# dragonjoy.net
KiCad netlist of a schematic drawn in EAGLE
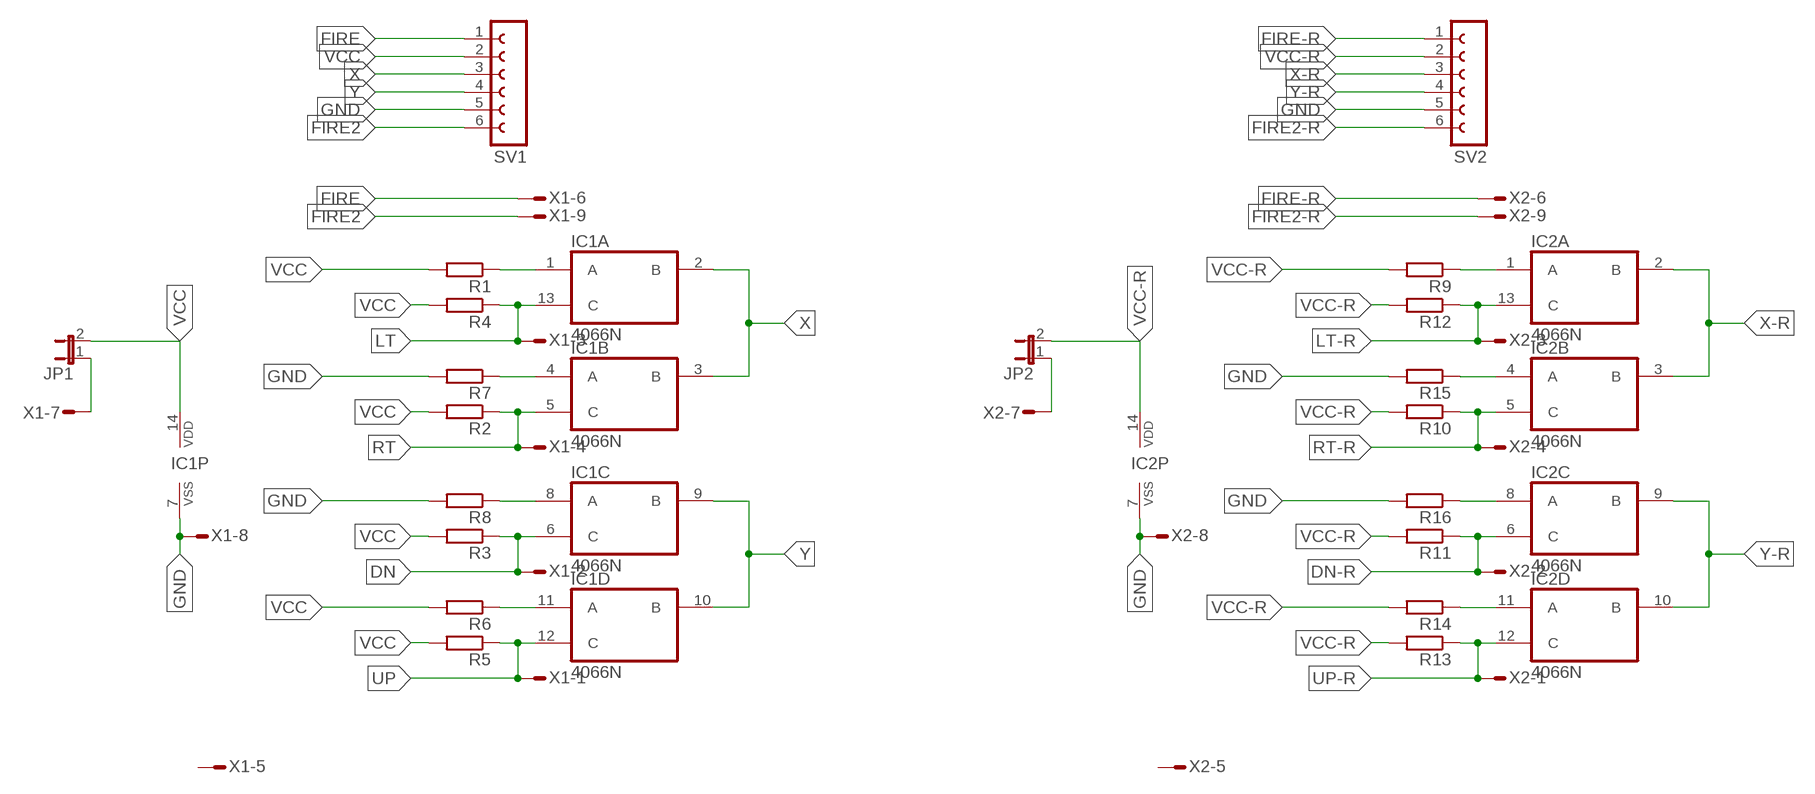
[diagram p0: schematic, sheet 1]

(export (version "E")
  (design (tool "Eeschema 10.0.6"))
  (components
    (comp (ref "IC1")
      (value "4066N")
      (footprint "eagle-import:DIL14")
      (libsource (lib "eagle-import") (part "4066N"))
    )
    (comp (ref "IC2")
      (value "4066N")
      (footprint "eagle-import:DIL14")
      (libsource (lib "eagle-import") (part "4066N"))
    )
    (comp (ref "JP1")
      (value "JP1E")
      (footprint "eagle-import:JP1")
      (libsource (lib "eagle-import") (part "JP1E"))
    )
    (comp (ref "JP2")
      (value "JP1E")
      (footprint "eagle-import:JP1")
      (libsource (lib "eagle-import") (part "JP1E"))
    )
    (comp (ref "R1")
      (value "R-EU_0207/10")
      (footprint "eagle-import:0207_10")
      (libsource (lib "eagle-import") (part "R-EU_0207/10"))
    )
    (comp (ref "R2")
      (value "R-EU_0207/10")
      (footprint "eagle-import:0207_10")
      (libsource (lib "eagle-import") (part "R-EU_0207/10"))
    )
    (comp (ref "R3")
      (value "R-EU_0207/10")
      (footprint "eagle-import:0207_10")
      (libsource (lib "eagle-import") (part "R-EU_0207/10"))
    )
    (comp (ref "R4")
      (value "R-EU_0207/10")
      (footprint "eagle-import:0207_10")
      (libsource (lib "eagle-import") (part "R-EU_0207/10"))
    )
    (comp (ref "R5")
      (value "R-EU_0207/10")
      (footprint "eagle-import:0207_10")
      (libsource (lib "eagle-import") (part "R-EU_0207/10"))
    )
    (comp (ref "R6")
      (value "R-EU_0207/10")
      (footprint "eagle-import:0207_10")
      (libsource (lib "eagle-import") (part "R-EU_0207/10"))
    )
    (comp (ref "R7")
      (value "R-EU_0207/10")
      (footprint "eagle-import:0207_10")
      (libsource (lib "eagle-import") (part "R-EU_0207/10"))
    )
    (comp (ref "R8")
      (value "R-EU_0207/10")
      (footprint "eagle-import:0207_10")
      (libsource (lib "eagle-import") (part "R-EU_0207/10"))
    )
    (comp (ref "R9")
      (value "R-EU_0207/10")
      (footprint "eagle-import:0207_10")
      (libsource (lib "eagle-import") (part "R-EU_0207/10"))
    )
    (comp (ref "R10")
      (value "R-EU_0207/10")
      (footprint "eagle-import:0207_10")
      (libsource (lib "eagle-import") (part "R-EU_0207/10"))
    )
    (comp (ref "R11")
      (value "R-EU_0207/10")
      (footprint "eagle-import:0207_10")
      (libsource (lib "eagle-import") (part "R-EU_0207/10"))
    )
    (comp (ref "R12")
      (value "R-EU_0207/10")
      (footprint "eagle-import:0207_10")
      (libsource (lib "eagle-import") (part "R-EU_0207/10"))
    )
    (comp (ref "R13")
      (value "R-EU_0207/10")
      (footprint "eagle-import:0207_10")
      (libsource (lib "eagle-import") (part "R-EU_0207/10"))
    )
    (comp (ref "R14")
      (value "R-EU_0207/10")
      (footprint "eagle-import:0207_10")
      (libsource (lib "eagle-import") (part "R-EU_0207/10"))
    )
    (comp (ref "R15")
      (value "R-EU_0207/10")
      (footprint "eagle-import:0207_10")
      (libsource (lib "eagle-import") (part "R-EU_0207/10"))
    )
    (comp (ref "R16")
      (value "R-EU_0207/10")
      (footprint "eagle-import:0207_10")
      (libsource (lib "eagle-import") (part "R-EU_0207/10"))
    )
    (comp (ref "SV1")
      (value "FE06-1")
      (footprint "eagle-import:FE06")
      (libsource (lib "eagle-import") (part "FE06-1"))
    )
    (comp (ref "SV2")
      (value "FE06-1")
      (footprint "eagle-import:FE06")
      (libsource (lib "eagle-import") (part "FE06-1"))
    )
    (comp (ref "X1")
      (value "M09-182S")
      (footprint "eagle-import:182-009-MALE")
      (libsource (lib "eagle-import") (part "M09?S-182"))
    )
    (comp (ref "X2")
      (value "M09-182S")
      (footprint "eagle-import:182-009-MALE")
      (libsource (lib "eagle-import") (part "M09?S-182"))
    )
  )
  (nets
    (net (code "1") (name "DN") (class "Default")
      (node (ref "IC1") (pin "6") (pinfunction "C_6") (pintype "input"))
      (node (ref "R3") (pin "1") (pinfunction "1_1") (pintype "passive"))
      (node (ref "X1") (pin "2") (pinfunction "M_2") (pintype "passive"))
    )
    (net (code "2") (name "DN-R") (class "Default")
      (node (ref "IC2") (pin "6") (pinfunction "C_6") (pintype "input"))
      (node (ref "R11") (pin "1") (pinfunction "1_1") (pintype "passive"))
      (node (ref "X2") (pin "2") (pinfunction "M_2") (pintype "passive"))
    )
    (net (code "3") (name "FIRE") (class "Default")
      (node (ref "SV1") (pin "1") (pinfunction "1_1") (pintype "passive"))
      (node (ref "X1") (pin "6") (pinfunction "M_6") (pintype "passive"))
    )
    (net (code "4") (name "FIRE-R") (class "Default")
      (node (ref "SV2") (pin "1") (pinfunction "1_1") (pintype "passive"))
      (node (ref "X2") (pin "6") (pinfunction "M_6") (pintype "passive"))
    )
    (net (code "5") (name "FIRE2") (class "Default")
      (node (ref "SV1") (pin "6") (pinfunction "6_6") (pintype "passive"))
      (node (ref "X1") (pin "9") (pinfunction "M_9") (pintype "passive"))
    )
    (net (code "6") (name "FIRE2-R") (class "Default")
      (node (ref "SV2") (pin "6") (pinfunction "6_6") (pintype "passive"))
      (node (ref "X2") (pin "9") (pinfunction "M_9") (pintype "passive"))
    )
    (net (code "7") (name "GND") (class "Default")
      (node (ref "IC1") (pin "7") (pinfunction "VSS_7") (pintype "power_in"))
      (node (ref "IC2") (pin "7") (pinfunction "VSS_7") (pintype "power_in"))
      (node (ref "R15") (pin "2") (pinfunction "2_2") (pintype "passive"))
      (node (ref "R16") (pin "2") (pinfunction "2_2") (pintype "passive"))
      (node (ref "R7") (pin "2") (pinfunction "2_2") (pintype "passive"))
      (node (ref "R8") (pin "2") (pinfunction "2_2") (pintype "passive"))
      (node (ref "SV1") (pin "5") (pinfunction "5_5") (pintype "passive"))
      (node (ref "SV2") (pin "5") (pinfunction "5_5") (pintype "passive"))
      (node (ref "X1") (pin "8") (pinfunction "M_8") (pintype "passive"))
      (node (ref "X2") (pin "8") (pinfunction "M_8") (pintype "passive"))
    )
    (net (code "8") (name "LT") (class "Default")
      (node (ref "IC1") (pin "13") (pinfunction "C_13") (pintype "input"))
      (node (ref "R4") (pin "1") (pinfunction "1_1") (pintype "passive"))
      (node (ref "X1") (pin "3") (pinfunction "M_3") (pintype "passive"))
    )
    (net (code "9") (name "LT-R") (class "Default")
      (node (ref "IC2") (pin "13") (pinfunction "C_13") (pintype "input"))
      (node (ref "R12") (pin "1") (pinfunction "1_1") (pintype "passive"))
      (node (ref "X2") (pin "3") (pinfunction "M_3") (pintype "passive"))
    )
    (net (code "10") (name "Net-(IC1A-A)") (class "Default")
      (node (ref "IC1") (pin "1") (pinfunction "A_1") (pintype "tri_state"))
      (node (ref "R1") (pin "1") (pinfunction "1_1") (pintype "passive"))
    )
    (net (code "11") (name "Net-(IC1B-A)") (class "Default")
      (node (ref "IC1") (pin "4") (pinfunction "A_4") (pintype "tri_state"))
      (node (ref "R7") (pin "1") (pinfunction "1_1") (pintype "passive"))
    )
    (net (code "12") (name "Net-(IC1C-A)") (class "Default")
      (node (ref "IC1") (pin "8") (pinfunction "A_8") (pintype "tri_state"))
      (node (ref "R8") (pin "1") (pinfunction "1_1") (pintype "passive"))
    )
    (net (code "13") (name "Net-(IC1D-A)") (class "Default")
      (node (ref "IC1") (pin "11") (pinfunction "A_11") (pintype "tri_state"))
      (node (ref "R6") (pin "1") (pinfunction "1_1") (pintype "passive"))
    )
    (net (code "14") (name "Net-(IC2A-A)") (class "Default")
      (node (ref "IC2") (pin "1") (pinfunction "A_1") (pintype "tri_state"))
      (node (ref "R9") (pin "1") (pinfunction "1_1") (pintype "passive"))
    )
    (net (code "15") (name "Net-(IC2B-A)") (class "Default")
      (node (ref "IC2") (pin "4") (pinfunction "A_4") (pintype "tri_state"))
      (node (ref "R15") (pin "1") (pinfunction "1_1") (pintype "passive"))
    )
    (net (code "16") (name "Net-(IC2C-A)") (class "Default")
      (node (ref "IC2") (pin "8") (pinfunction "A_8") (pintype "tri_state"))
      (node (ref "R16") (pin "1") (pinfunction "1_1") (pintype "passive"))
    )
    (net (code "17") (name "Net-(IC2D-A)") (class "Default")
      (node (ref "IC2") (pin "11") (pinfunction "A_11") (pintype "tri_state"))
      (node (ref "R14") (pin "1") (pinfunction "1_1") (pintype "passive"))
    )
    (net (code "18") (name "Net-(X1G-M)") (class "Default")
      (node (ref "JP1") (pin "1") (pinfunction "1_1") (pintype "passive"))
      (node (ref "X1") (pin "7") (pinfunction "M_7") (pintype "passive"))
    )
    (net (code "19") (name "Net-(X2G-M)") (class "Default")
      (node (ref "JP2") (pin "1") (pinfunction "1_1") (pintype "passive"))
      (node (ref "X2") (pin "7") (pinfunction "M_7") (pintype "passive"))
    )
    (net (code "20") (name "RT") (class "Default")
      (node (ref "IC1") (pin "5") (pinfunction "C_5") (pintype "input"))
      (node (ref "R2") (pin "1") (pinfunction "1_1") (pintype "passive"))
      (node (ref "X1") (pin "4") (pinfunction "M_4") (pintype "passive"))
    )
    (net (code "21") (name "RT-R") (class "Default")
      (node (ref "IC2") (pin "5") (pinfunction "C_5") (pintype "input"))
      (node (ref "R10") (pin "1") (pinfunction "1_1") (pintype "passive"))
      (node (ref "X2") (pin "4") (pinfunction "M_4") (pintype "passive"))
    )
    (net (code "22") (name "UP") (class "Default")
      (node (ref "IC1") (pin "12") (pinfunction "C_12") (pintype "input"))
      (node (ref "R5") (pin "1") (pinfunction "1_1") (pintype "passive"))
      (node (ref "X1") (pin "1") (pinfunction "M_1") (pintype "passive"))
    )
    (net (code "23") (name "UP-R") (class "Default")
      (node (ref "IC2") (pin "12") (pinfunction "C_12") (pintype "input"))
      (node (ref "R13") (pin "1") (pinfunction "1_1") (pintype "passive"))
      (node (ref "X2") (pin "1") (pinfunction "M_1") (pintype "passive"))
    )
    (net (code "24") (name "VCC") (class "Default")
      (node (ref "IC1") (pin "14") (pinfunction "VDD_14") (pintype "power_in"))
      (node (ref "JP1") (pin "2") (pinfunction "2_2") (pintype "passive"))
      (node (ref "R1") (pin "2") (pinfunction "2_2") (pintype "passive"))
      (node (ref "R2") (pin "2") (pinfunction "2_2") (pintype "passive"))
      (node (ref "R3") (pin "2") (pinfunction "2_2") (pintype "passive"))
      (node (ref "R4") (pin "2") (pinfunction "2_2") (pintype "passive"))
      (node (ref "R5") (pin "2") (pinfunction "2_2") (pintype "passive"))
      (node (ref "R6") (pin "2") (pinfunction "2_2") (pintype "passive"))
      (node (ref "SV1") (pin "2") (pinfunction "2_2") (pintype "passive"))
    )
    (net (code "25") (name "VCC-R") (class "Default")
      (node (ref "IC2") (pin "14") (pinfunction "VDD_14") (pintype "power_in"))
      (node (ref "JP2") (pin "2") (pinfunction "2_2") (pintype "passive"))
      (node (ref "R10") (pin "2") (pinfunction "2_2") (pintype "passive"))
      (node (ref "R11") (pin "2") (pinfunction "2_2") (pintype "passive"))
      (node (ref "R12") (pin "2") (pinfunction "2_2") (pintype "passive"))
      (node (ref "R13") (pin "2") (pinfunction "2_2") (pintype "passive"))
      (node (ref "R14") (pin "2") (pinfunction "2_2") (pintype "passive"))
      (node (ref "R9") (pin "2") (pinfunction "2_2") (pintype "passive"))
      (node (ref "SV2") (pin "2") (pinfunction "2_2") (pintype "passive"))
    )
    (net (code "26") (name "X") (class "Default")
      (node (ref "IC1") (pin "2") (pinfunction "B_2") (pintype "tri_state"))
      (node (ref "IC1") (pin "3") (pinfunction "B_3") (pintype "tri_state"))
      (node (ref "SV1") (pin "3") (pinfunction "3_3") (pintype "passive"))
    )
    (net (code "27") (name "X-R") (class "Default")
      (node (ref "IC2") (pin "2") (pinfunction "B_2") (pintype "tri_state"))
      (node (ref "IC2") (pin "3") (pinfunction "B_3") (pintype "tri_state"))
      (node (ref "SV2") (pin "3") (pinfunction "3_3") (pintype "passive"))
    )
    (net (code "28") (name "Y") (class "Default")
      (node (ref "IC1") (pin "10") (pinfunction "B_10") (pintype "tri_state"))
      (node (ref "IC1") (pin "9") (pinfunction "B_9") (pintype "tri_state"))
      (node (ref "SV1") (pin "4") (pinfunction "4_4") (pintype "passive"))
    )
    (net (code "29") (name "Y-R") (class "Default")
      (node (ref "IC2") (pin "10") (pinfunction "B_10") (pintype "tri_state"))
      (node (ref "IC2") (pin "9") (pinfunction "B_9") (pintype "tri_state"))
      (node (ref "SV2") (pin "4") (pinfunction "4_4") (pintype "passive"))
    )
    (net (code "30") (name "unconnected-(X1E-M-Pad5)") (class "Default")
      (node (ref "X1") (pin "5") (pinfunction "M_5") (pintype "passive"))
    )
    (net (code "31") (name "unconnected-(X2E-M-Pad5)") (class "Default")
      (node (ref "X2") (pin "5") (pinfunction "M_5") (pintype "passive"))
    )
  )
)
